# sw.net
KiCad netlist of a schematic drawn in Altium Designer
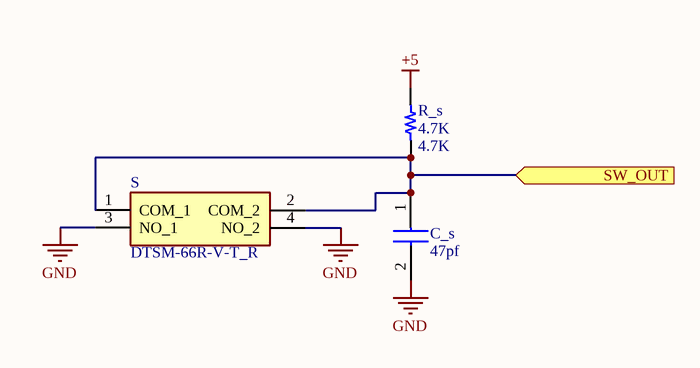
[diagram p0: sw.SchDoc]

(export (version "E")
  (design (tool "Eeschema 10.0.6"))
  (components
    (comp (ref "C_s")
      (value "47pf")
      (footprint "0603C")
      (description "100 nF Ceramic capacitor")
      (fields
        (field (name "MANUFACTURER_PART_NUMBER") "C1206C104Z5UACTU")
        (field (name "MOUSER PART NUMBER") "80-C1206C104Z5U")
      )
      (libsource (lib "*") (part "C1206C104Z5UACTU"))
    )
    (comp (ref "R_s")
      (value "4.7K")
      (footprint "0603R")
      (description "RES SMD 100K OHM 1% 0.4W 0805")
      (fields (field (name "PART NUMBER") "RCS0805100KFKEA") (field (name "ALTIUM_VALUE") "4.7K"))
      (libsource (lib "lamp control-ver2") (part "Resistor"))
    )
    (comp (ref "S")
      (value "DTSM-66R-V-T_R")
      (footprint "SamacSys:DTSM63NVB")
      (description "Switch")
      (fields
        (field (name "MANUFACTURER_PART_NUMBER") "DTSM-66R-V-T/R")
        (field (name "MOUSER PART NUMBER") "113-DTSM66RVTR")
      )
      (libsource (lib "*") (part "DTSM-66R-V-T_R"))
    )
  )
  (nets
    (net (code "1") (name "+5") (class "Default")
      (node (ref "R_s") (pin "2") (pinfunction "2_2") (pintype "passive"))
    )
    (net (code "2") (name "/SW_OUT") (class "Default")
      (node (ref "C_s") (pin "1") (pinfunction "1_1") (pintype "passive"))
      (node (ref "R_s") (pin "1") (pinfunction "1_1") (pintype "passive"))
      (node (ref "S") (pin "1") (pinfunction "COM_1_1") (pintype "passive"))
      (node (ref "S") (pin "2") (pinfunction "COM_2_2") (pintype "passive"))
    )
    (net (code "3") (name "GND") (class "Default")
      (node (ref "C_s") (pin "2") (pinfunction "2_2") (pintype "passive"))
      (node (ref "S") (pin "3") (pinfunction "NO_1_3") (pintype "passive"))
      (node (ref "S") (pin "4") (pinfunction "NO_2_4") (pintype "passive"))
    )
  )
)
